# vest.net
KiCad netlist of a schematic drawn in EAGLE
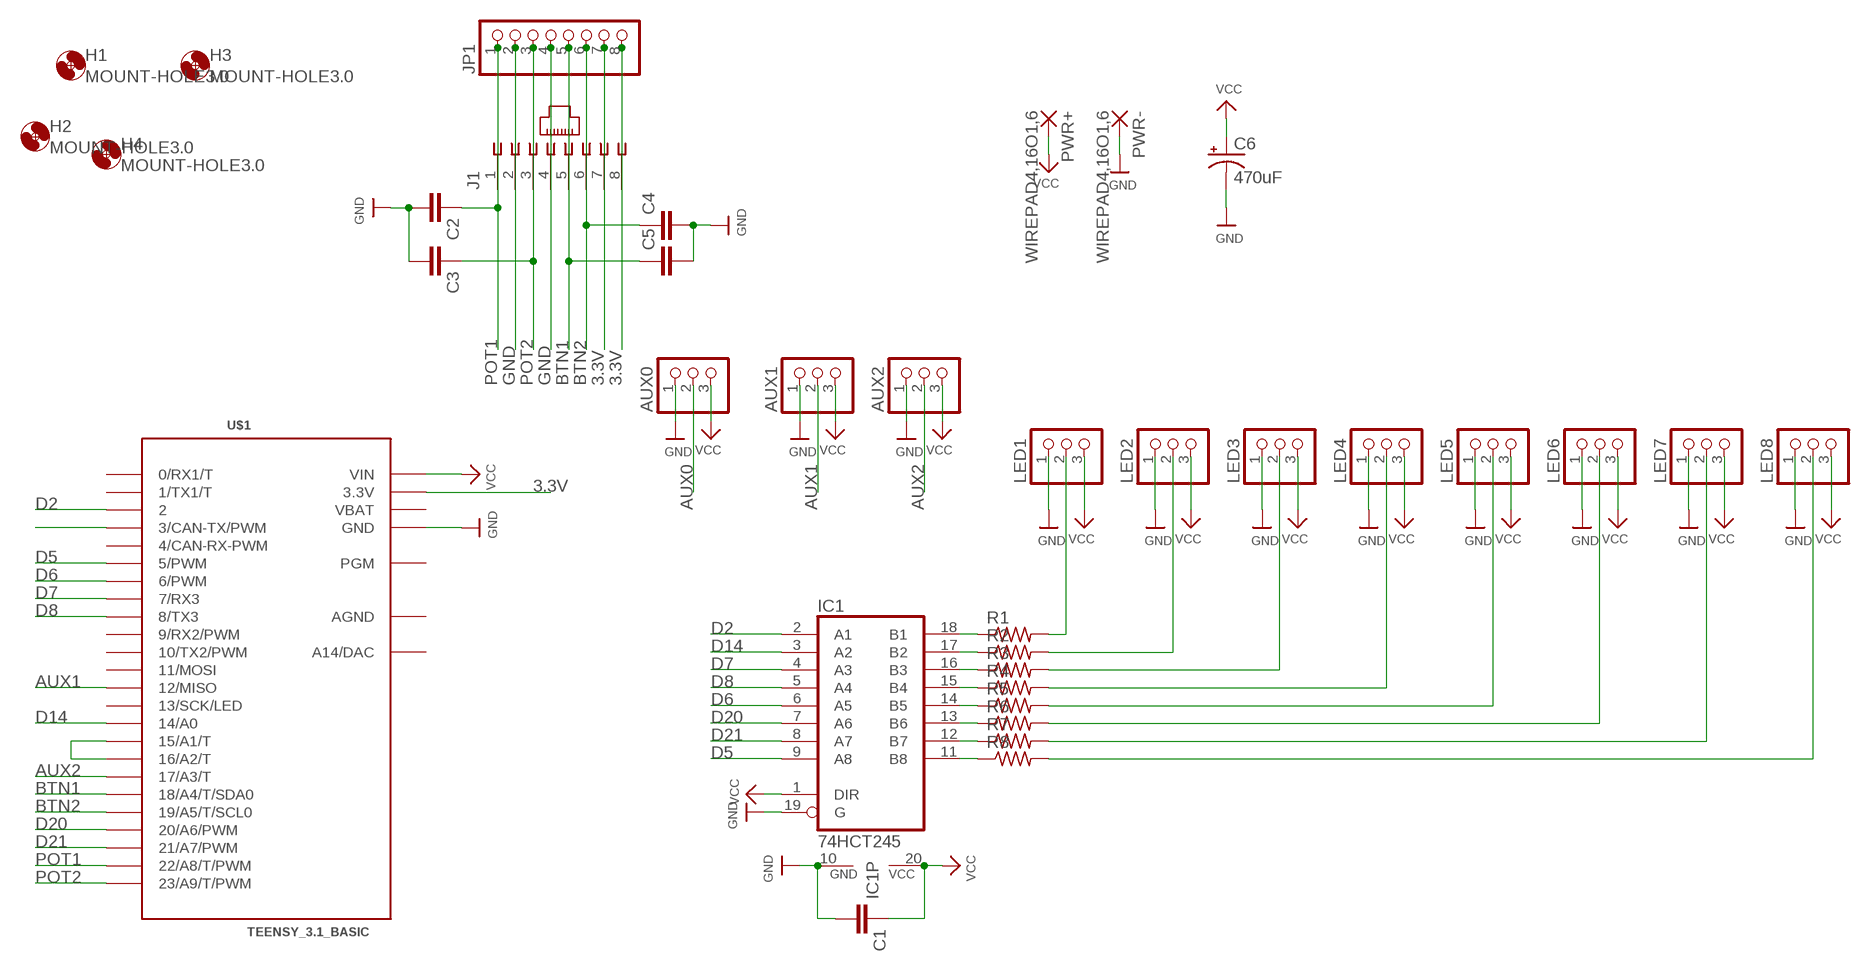
[diagram p0: schematic, sheet 1]

(export (version "E")
  (design (tool "Eeschema 10.0.6"))
  (components
    (comp (ref "AUX0")
      (value "HEADER-1X3")
      (footprint "eagle-import:1X03_OVAL")
      (libsource (lib "eagle-import") (part "HEADER-1X3"))
    )
    (comp (ref "AUX1")
      (value "HEADER-1X3")
      (footprint "eagle-import:1X03_OVAL")
      (libsource (lib "eagle-import") (part "HEADER-1X3"))
    )
    (comp (ref "AUX2")
      (value "HEADER-1X3")
      (footprint "eagle-import:1X03_OVAL")
      (libsource (lib "eagle-import") (part "HEADER-1X3"))
    )
    (comp (ref "C1")
      (value "C-EU025-025X050")
      (footprint "eagle-import:C025-025X050")
      (libsource (lib "eagle-import") (part "C-EU025-025X050"))
    )
    (comp (ref "C2")
      (value "C-EU025-025X050")
      (footprint "eagle-import:C025-025X050")
      (libsource (lib "eagle-import") (part "C-EU025-025X050"))
    )
    (comp (ref "C3")
      (value "C-EU025-025X050")
      (footprint "eagle-import:C025-025X050")
      (libsource (lib "eagle-import") (part "C-EU025-025X050"))
    )
    (comp (ref "C4")
      (value "C-EU025-025X050")
      (footprint "eagle-import:C025-025X050")
      (libsource (lib "eagle-import") (part "C-EU025-025X050"))
    )
    (comp (ref "C5")
      (value "C-EU025-025X050")
      (footprint "eagle-import:C025-025X050")
      (libsource (lib "eagle-import") (part "C-EU025-025X050"))
    )
    (comp (ref "C6")
      (value "470uF")
      (footprint "eagle-import:TT2D7L")
      (libsource (lib "eagle-import") (part "CPOL-USTT2D7L"))
    )
    (comp (ref "H1")
      (value "MOUNT-HOLE3.0")
      (footprint "eagle-import:3,0")
      (libsource (lib "eagle-import") (part "MOUNT-HOLE3.0"))
    )
    (comp (ref "H2")
      (value "MOUNT-HOLE3.0")
      (footprint "eagle-import:3,0")
      (libsource (lib "eagle-import") (part "MOUNT-HOLE3.0"))
    )
    (comp (ref "H3")
      (value "MOUNT-HOLE3.0")
      (footprint "eagle-import:3,0")
      (libsource (lib "eagle-import") (part "MOUNT-HOLE3.0"))
    )
    (comp (ref "H4")
      (value "MOUNT-HOLE3.0")
      (footprint "eagle-import:3,0")
      (libsource (lib "eagle-import") (part "MOUNT-HOLE3.0"))
    )
    (comp (ref "IC1")
      (value "74HCT245")
      (footprint "eagle-import:DIL20")
      (libsource (lib "eagle-import") (part "74245NAC"))
    )
    (comp (ref "J1")
      (value "215877-4")
      (footprint "eagle-import:215877-4")
      (libsource (lib "eagle-import") (part "215877-4"))
    )
    (comp (ref "JP1")
      (value "HEADER-1X870MIL")
      (footprint "eagle-import:1X08_ROUND_70")
      (libsource (lib "eagle-import") (part "HEADER-1X870MIL"))
    )
    (comp (ref "LED1")
      (value "HEADER-1X3")
      (footprint "eagle-import:1X03_OVAL")
      (libsource (lib "eagle-import") (part "HEADER-1X3"))
    )
    (comp (ref "LED2")
      (value "HEADER-1X3")
      (footprint "eagle-import:1X03_OVAL")
      (libsource (lib "eagle-import") (part "HEADER-1X3"))
    )
    (comp (ref "LED3")
      (value "HEADER-1X3")
      (footprint "eagle-import:1X03_OVAL")
      (libsource (lib "eagle-import") (part "HEADER-1X3"))
    )
    (comp (ref "LED4")
      (value "HEADER-1X3")
      (footprint "eagle-import:1X03_OVAL")
      (libsource (lib "eagle-import") (part "HEADER-1X3"))
    )
    (comp (ref "LED5")
      (value "HEADER-1X3")
      (footprint "eagle-import:1X03_OVAL")
      (libsource (lib "eagle-import") (part "HEADER-1X3"))
    )
    (comp (ref "LED6")
      (value "HEADER-1X3")
      (footprint "eagle-import:1X03_OVAL")
      (libsource (lib "eagle-import") (part "HEADER-1X3"))
    )
    (comp (ref "LED7")
      (value "HEADER-1X3")
      (footprint "eagle-import:1X03_OVAL")
      (libsource (lib "eagle-import") (part "HEADER-1X3"))
    )
    (comp (ref "LED8")
      (value "HEADER-1X3")
      (footprint "eagle-import:1X03_OVAL")
      (libsource (lib "eagle-import") (part "HEADER-1X3"))
    )
    (comp (ref "PWR+")
      (value "WIREPAD4,16O1,6")
      (footprint "eagle-import:4,16O1,6")
      (libsource (lib "eagle-import") (part "WIREPAD4,16O1,6"))
    )
    (comp (ref "PWR-")
      (value "WIREPAD4,16O1,6")
      (footprint "eagle-import:4,16O1,6")
      (libsource (lib "eagle-import") (part "WIREPAD4,16O1,6"))
    )
    (comp (ref "R1")
      (value "R-US_0204/7")
      (footprint "eagle-import:0204_7")
      (libsource (lib "eagle-import") (part "R-US_0204/7"))
    )
    (comp (ref "R2")
      (value "R-US_0204/7")
      (footprint "eagle-import:0204_7")
      (libsource (lib "eagle-import") (part "R-US_0204/7"))
    )
    (comp (ref "R3")
      (value "R-US_0204/7")
      (footprint "eagle-import:0204_7")
      (libsource (lib "eagle-import") (part "R-US_0204/7"))
    )
    (comp (ref "R4")
      (value "R-US_0204/7")
      (footprint "eagle-import:0204_7")
      (libsource (lib "eagle-import") (part "R-US_0204/7"))
    )
    (comp (ref "R5")
      (value "R-US_0204/7")
      (footprint "eagle-import:0204_7")
      (libsource (lib "eagle-import") (part "R-US_0204/7"))
    )
    (comp (ref "R6")
      (value "R-US_0204/7")
      (footprint "eagle-import:0204_7")
      (libsource (lib "eagle-import") (part "R-US_0204/7"))
    )
    (comp (ref "R7")
      (value "R-US_0204/7")
      (footprint "eagle-import:0204_7")
      (libsource (lib "eagle-import") (part "R-US_0204/7"))
    )
    (comp (ref "R8")
      (value "R-US_0204/7")
      (footprint "eagle-import:0204_7")
      (libsource (lib "eagle-import") (part "R-US_0204/7"))
    )
    (comp (ref "U$1")
      (value "TEENSY_3.1_BASIC")
      (footprint "eagle-import:TEENSY_3.1_BASIC")
      (libsource (lib "eagle-import") (part "TEENSY_3.1_BASIC"))
    )
  )
  (nets
    (net (code "1") (name "/3.3V") (class "Default")
      (node (ref "J1") (pin "7") (pinfunction "7_7") (pintype "passive"))
      (node (ref "J1") (pin "8") (pinfunction "8_8") (pintype "passive"))
      (node (ref "JP1") (pin "7") (pinfunction "7_7") (pintype "passive"))
      (node (ref "JP1") (pin "8") (pinfunction "8_8") (pintype "passive"))
      (node (ref "U$1") (pin "3.3V") (pinfunction "3.3V_3.3V") (pintype "power_in"))
      (node (ref "U$1") (pin "3.3V1") (pinfunction "3.3V_3.3V1") (pintype "power_in"))
    )
    (net (code "2") (name "/AGND") (class "Default")
      (node (ref "U$1") (pin "AGND") (pinfunction "AGND_AGND") (pintype "power_in"))
    )
    (net (code "3") (name "/AUX0") (class "Default")
      (node (ref "AUX0") (pin "2") (pinfunction "2_2") (pintype "passive"))
      (node (ref "U$1") (pin "3") (pinfunction "3/CAN-TX/PWM_3") (pintype "bidirectional"))
    )
    (net (code "4") (name "/AUX1") (class "Default")
      (node (ref "AUX1") (pin "2") (pinfunction "2_2") (pintype "passive"))
      (node (ref "U$1") (pin "12") (pinfunction "12/MISO_12") (pintype "bidirectional"))
    )
    (net (code "5") (name "/AUX2") (class "Default")
      (node (ref "AUX2") (pin "2") (pinfunction "2_2") (pintype "passive"))
      (node (ref "U$1") (pin "17/A3") (pinfunction "17/A3/T_17/A3") (pintype "bidirectional"))
    )
    (net (code "6") (name "/BTN1") (class "Default")
      (node (ref "C5") (pin "1") (pinfunction "1_1") (pintype "passive"))
      (node (ref "J1") (pin "5") (pinfunction "5_5") (pintype "passive"))
      (node (ref "JP1") (pin "5") (pinfunction "5_5") (pintype "passive"))
      (node (ref "U$1") (pin "18/A4") (pinfunction "18/A4/T/SDA0_18/A4") (pintype "bidirectional"))
    )
    (net (code "7") (name "/BTN2") (class "Default")
      (node (ref "C4") (pin "1") (pinfunction "1_1") (pintype "passive"))
      (node (ref "J1") (pin "6") (pinfunction "6_6") (pintype "passive"))
      (node (ref "JP1") (pin "6") (pinfunction "6_6") (pintype "passive"))
      (node (ref "U$1") (pin "19/A5") (pinfunction "19/A5/T/SCL0_19/A5") (pintype "bidirectional"))
    )
    (net (code "8") (name "/D2") (class "Default")
      (node (ref "IC1") (pin "2") (pinfunction "A1_2") (pintype "bidirectional"))
      (node (ref "U$1") (pin "2") (pinfunction "2_2") (pintype "bidirectional"))
    )
    (net (code "9") (name "/D5") (class "Default")
      (node (ref "IC1") (pin "9") (pinfunction "A8_9") (pintype "bidirectional"))
      (node (ref "U$1") (pin "5") (pinfunction "5/PWM_5") (pintype "bidirectional"))
    )
    (net (code "10") (name "/D6") (class "Default")
      (node (ref "IC1") (pin "6") (pinfunction "A5_6") (pintype "bidirectional"))
      (node (ref "U$1") (pin "6") (pinfunction "6/PWM_6") (pintype "bidirectional"))
    )
    (net (code "11") (name "/D7") (class "Default")
      (node (ref "IC1") (pin "4") (pinfunction "A3_4") (pintype "bidirectional"))
      (node (ref "U$1") (pin "7") (pinfunction "7/RX3_7") (pintype "bidirectional"))
    )
    (net (code "12") (name "/D8") (class "Default")
      (node (ref "IC1") (pin "5") (pinfunction "A4_5") (pintype "bidirectional"))
      (node (ref "U$1") (pin "8") (pinfunction "8/TX3_8") (pintype "bidirectional"))
    )
    (net (code "13") (name "/D14") (class "Default")
      (node (ref "IC1") (pin "3") (pinfunction "A2_3") (pintype "bidirectional"))
      (node (ref "U$1") (pin "14/A0") (pinfunction "14/A0_14/A0") (pintype "bidirectional"))
    )
    (net (code "14") (name "/D20") (class "Default")
      (node (ref "IC1") (pin "7") (pinfunction "A6_7") (pintype "bidirectional"))
      (node (ref "U$1") (pin "20/A6") (pinfunction "20/A6/PWM_20/A6") (pintype "bidirectional"))
    )
    (net (code "15") (name "/D21") (class "Default")
      (node (ref "IC1") (pin "8") (pinfunction "A7_8") (pintype "bidirectional"))
      (node (ref "U$1") (pin "21/A7") (pinfunction "21/A7/PWM_21/A7") (pintype "bidirectional"))
    )
    (net (code "16") (name "/POT1") (class "Default")
      (node (ref "C2") (pin "1") (pinfunction "1_1") (pintype "passive"))
      (node (ref "J1") (pin "1") (pinfunction "1_1") (pintype "passive"))
      (node (ref "JP1") (pin "1") (pinfunction "1_1") (pintype "passive"))
      (node (ref "U$1") (pin "22/A8") (pinfunction "22/A8/T/PWM_22/A8") (pintype "bidirectional"))
    )
    (net (code "17") (name "/POT2") (class "Default")
      (node (ref "C3") (pin "1") (pinfunction "1_1") (pintype "passive"))
      (node (ref "J1") (pin "3") (pinfunction "3_3") (pintype "passive"))
      (node (ref "JP1") (pin "3") (pinfunction "3_3") (pintype "passive"))
      (node (ref "U$1") (pin "23/A9") (pinfunction "23/A9/T/PWM_23/A9") (pintype "bidirectional"))
    )
    (net (code "18") (name "/VBAT") (class "Default")
      (node (ref "U$1") (pin "VBAT") (pinfunction "VBAT_VBAT") (pintype "power_in"))
    )
    (net (code "19") (name "GND") (class "Default")
      (node (ref "AUX0") (pin "1") (pinfunction "1_1") (pintype "passive"))
      (node (ref "AUX1") (pin "1") (pinfunction "1_1") (pintype "passive"))
      (node (ref "AUX2") (pin "1") (pinfunction "1_1") (pintype "passive"))
      (node (ref "C1") (pin "2") (pinfunction "2_2") (pintype "passive"))
      (node (ref "C2") (pin "2") (pinfunction "2_2") (pintype "passive"))
      (node (ref "C3") (pin "2") (pinfunction "2_2") (pintype "passive"))
      (node (ref "C4") (pin "2") (pinfunction "2_2") (pintype "passive"))
      (node (ref "C5") (pin "2") (pinfunction "2_2") (pintype "passive"))
      (node (ref "C6") (pin "-") (pinfunction "-_-") (pintype "passive"))
      (node (ref "IC1") (pin "10") (pinfunction "GND_10") (pintype "power_in"))
      (node (ref "IC1") (pin "19") (pinfunction "G_19") (pintype "input"))
      (node (ref "J1") (pin "2") (pinfunction "2_2") (pintype "passive"))
      (node (ref "J1") (pin "4") (pinfunction "4_4") (pintype "passive"))
      (node (ref "JP1") (pin "2") (pinfunction "2_2") (pintype "passive"))
      (node (ref "JP1") (pin "4") (pinfunction "4_4") (pintype "passive"))
      (node (ref "LED1") (pin "1") (pinfunction "1_1") (pintype "passive"))
      (node (ref "LED2") (pin "1") (pinfunction "1_1") (pintype "passive"))
      (node (ref "LED3") (pin "1") (pinfunction "1_1") (pintype "passive"))
      (node (ref "LED4") (pin "1") (pinfunction "1_1") (pintype "passive"))
      (node (ref "LED5") (pin "1") (pinfunction "1_1") (pintype "passive"))
      (node (ref "LED6") (pin "1") (pinfunction "1_1") (pintype "passive"))
      (node (ref "LED7") (pin "1") (pinfunction "1_1") (pintype "passive"))
      (node (ref "LED8") (pin "1") (pinfunction "1_1") (pintype "passive"))
      (node (ref "PWR-") (pin "1") (pinfunction "P_1") (pintype "passive"))
      (node (ref "U$1") (pin "GND") (pinfunction "GND_GND") (pintype "power_in"))
      (node (ref "U$1") (pin "GND1") (pinfunction "GND_GND1") (pintype "power_in"))
    )
    (net (code "20") (name "Net-(IC1A-B1)") (class "Default")
      (node (ref "IC1") (pin "18") (pinfunction "B1_18") (pintype "bidirectional"))
      (node (ref "R1") (pin "1") (pinfunction "1_1") (pintype "passive"))
    )
    (net (code "21") (name "Net-(IC1A-B2)") (class "Default")
      (node (ref "IC1") (pin "17") (pinfunction "B2_17") (pintype "bidirectional"))
      (node (ref "R2") (pin "1") (pinfunction "1_1") (pintype "passive"))
    )
    (net (code "22") (name "Net-(IC1A-B3)") (class "Default")
      (node (ref "IC1") (pin "16") (pinfunction "B3_16") (pintype "bidirectional"))
      (node (ref "R3") (pin "1") (pinfunction "1_1") (pintype "passive"))
    )
    (net (code "23") (name "Net-(IC1A-B4)") (class "Default")
      (node (ref "IC1") (pin "15") (pinfunction "B4_15") (pintype "bidirectional"))
      (node (ref "R4") (pin "1") (pinfunction "1_1") (pintype "passive"))
    )
    (net (code "24") (name "Net-(IC1A-B5)") (class "Default")
      (node (ref "IC1") (pin "14") (pinfunction "B5_14") (pintype "bidirectional"))
      (node (ref "R5") (pin "1") (pinfunction "1_1") (pintype "passive"))
    )
    (net (code "25") (name "Net-(IC1A-B6)") (class "Default")
      (node (ref "IC1") (pin "13") (pinfunction "B6_13") (pintype "bidirectional"))
      (node (ref "R6") (pin "1") (pinfunction "1_1") (pintype "passive"))
    )
    (net (code "26") (name "Net-(IC1A-B7)") (class "Default")
      (node (ref "IC1") (pin "12") (pinfunction "B7_12") (pintype "bidirectional"))
      (node (ref "R7") (pin "1") (pinfunction "1_1") (pintype "passive"))
    )
    (net (code "27") (name "Net-(IC1A-B8)") (class "Default")
      (node (ref "IC1") (pin "11") (pinfunction "B8_11") (pintype "bidirectional"))
      (node (ref "R8") (pin "1") (pinfunction "1_1") (pintype "passive"))
    )
    (net (code "28") (name "Net-(LED1-Pad2)") (class "Default")
      (node (ref "LED1") (pin "2") (pinfunction "2_2") (pintype "passive"))
      (node (ref "R1") (pin "2") (pinfunction "2_2") (pintype "passive"))
    )
    (net (code "29") (name "Net-(LED2-Pad2)") (class "Default")
      (node (ref "LED2") (pin "2") (pinfunction "2_2") (pintype "passive"))
      (node (ref "R2") (pin "2") (pinfunction "2_2") (pintype "passive"))
    )
    (net (code "30") (name "Net-(LED3-Pad2)") (class "Default")
      (node (ref "LED3") (pin "2") (pinfunction "2_2") (pintype "passive"))
      (node (ref "R3") (pin "2") (pinfunction "2_2") (pintype "passive"))
    )
    (net (code "31") (name "Net-(LED4-Pad2)") (class "Default")
      (node (ref "LED4") (pin "2") (pinfunction "2_2") (pintype "passive"))
      (node (ref "R4") (pin "2") (pinfunction "2_2") (pintype "passive"))
    )
    (net (code "32") (name "Net-(LED5-Pad2)") (class "Default")
      (node (ref "LED5") (pin "2") (pinfunction "2_2") (pintype "passive"))
      (node (ref "R5") (pin "2") (pinfunction "2_2") (pintype "passive"))
    )
    (net (code "33") (name "Net-(LED6-Pad2)") (class "Default")
      (node (ref "LED6") (pin "2") (pinfunction "2_2") (pintype "passive"))
      (node (ref "R6") (pin "2") (pinfunction "2_2") (pintype "passive"))
    )
    (net (code "34") (name "Net-(LED7-Pad2)") (class "Default")
      (node (ref "LED7") (pin "2") (pinfunction "2_2") (pintype "passive"))
      (node (ref "R7") (pin "2") (pinfunction "2_2") (pintype "passive"))
    )
    (net (code "35") (name "Net-(LED8-Pad2)") (class "Default")
      (node (ref "LED8") (pin "2") (pinfunction "2_2") (pintype "passive"))
      (node (ref "R8") (pin "2") (pinfunction "2_2") (pintype "passive"))
    )
    (net (code "36") (name "Net-(U$1-15{slash}A1{slash}T)") (class "Default")
      (node (ref "U$1") (pin "15/A1") (pinfunction "15/A1/T_15/A1") (pintype "bidirectional"))
      (node (ref "U$1") (pin "16/A2") (pinfunction "16/A2/T_16/A2") (pintype "bidirectional"))
    )
    (net (code "37") (name "VCC") (class "Default")
      (node (ref "AUX0") (pin "3") (pinfunction "3_3") (pintype "passive"))
      (node (ref "AUX1") (pin "3") (pinfunction "3_3") (pintype "passive"))
      (node (ref "AUX2") (pin "3") (pinfunction "3_3") (pintype "passive"))
      (node (ref "C1") (pin "1") (pinfunction "1_1") (pintype "passive"))
      (node (ref "C6") (pin "+") (pinfunction "+_+") (pintype "passive"))
      (node (ref "IC1") (pin "1") (pinfunction "DIR_1") (pintype "input"))
      (node (ref "IC1") (pin "20") (pinfunction "VCC_20") (pintype "power_in"))
      (node (ref "LED1") (pin "3") (pinfunction "3_3") (pintype "passive"))
      (node (ref "LED2") (pin "3") (pinfunction "3_3") (pintype "passive"))
      (node (ref "LED3") (pin "3") (pinfunction "3_3") (pintype "passive"))
      (node (ref "LED4") (pin "3") (pinfunction "3_3") (pintype "passive"))
      (node (ref "LED5") (pin "3") (pinfunction "3_3") (pintype "passive"))
      (node (ref "LED6") (pin "3") (pinfunction "3_3") (pintype "passive"))
      (node (ref "LED7") (pin "3") (pinfunction "3_3") (pintype "passive"))
      (node (ref "LED8") (pin "3") (pinfunction "3_3") (pintype "passive"))
      (node (ref "PWR+") (pin "1") (pinfunction "P_1") (pintype "passive"))
      (node (ref "U$1") (pin "VIN") (pinfunction "VIN_VIN") (pintype "power_in"))
    )
    (net (code "38") (name "unconnected-(U$1-0{slash}RX1{slash}T-Pad0)") (class "Default")
      (node (ref "U$1") (pin "0") (pinfunction "0/RX1/T_0") (pintype "bidirectional"))
    )
    (net (code "39") (name "unconnected-(U$1-1{slash}TX1{slash}T-Pad1)") (class "Default")
      (node (ref "U$1") (pin "1") (pinfunction "1/TX1/T_1") (pintype "bidirectional"))
    )
    (net (code "40") (name "unconnected-(U$1-4{slash}CAN-RX-PWM-Pad4)") (class "Default")
      (node (ref "U$1") (pin "4") (pinfunction "4/CAN-RX-PWM_4") (pintype "bidirectional"))
    )
    (net (code "41") (name "unconnected-(U$1-9{slash}RX2{slash}PWM-Pad9)") (class "Default")
      (node (ref "U$1") (pin "9") (pinfunction "9/RX2/PWM_9") (pintype "bidirectional"))
    )
    (net (code "42") (name "unconnected-(U$1-10{slash}TX2{slash}PWM-Pad10)") (class "Default")
      (node (ref "U$1") (pin "10") (pinfunction "10/TX2/PWM_10") (pintype "bidirectional"))
    )
    (net (code "43") (name "unconnected-(U$1-11{slash}MOSI-Pad11)") (class "Default")
      (node (ref "U$1") (pin "11") (pinfunction "11/MOSI_11") (pintype "bidirectional"))
    )
    (net (code "44") (name "unconnected-(U$1-13{slash}SCK{slash}LED-Pad13)") (class "Default")
      (node (ref "U$1") (pin "13") (pinfunction "13/SCK/LED_13") (pintype "bidirectional"))
    )
    (net (code "45") (name "unconnected-(U$1-A14{slash}DAC-PadA14)") (class "Default")
      (node (ref "U$1") (pin "A14") (pinfunction "A14/DAC_A14") (pintype "bidirectional"))
    )
    (net (code "46") (name "unconnected-(U$1-PadPGM)") (class "Default")
      (node (ref "U$1") (pin "PGM") (pinfunction "PGM_PGM") (pintype "bidirectional"))
    )
  )
)
